# Edge_Connector.net
KiCad netlist of a schematic drawn in Altium Designer
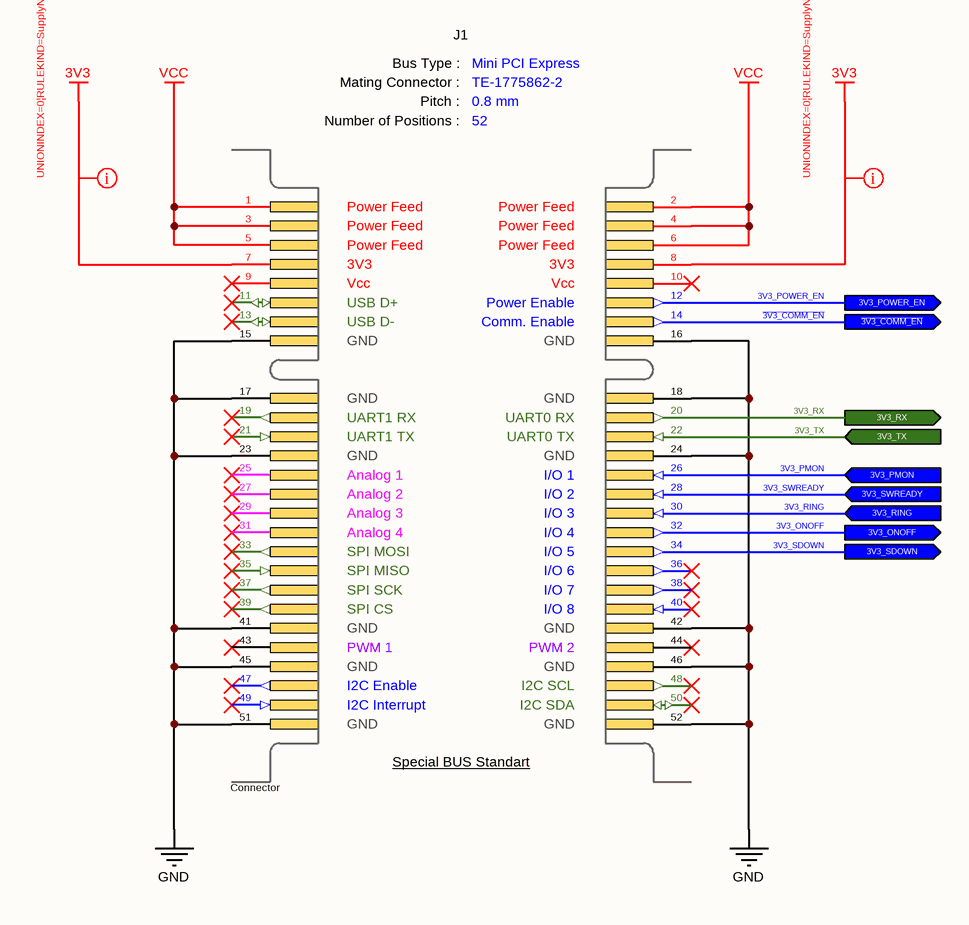
[diagram p0: Edge_Connector.SchDoc]

(export (version "E")
  (design (tool "Eeschema 10.0.6"))
  (components
    (comp (ref "J1")
      (value "Connector - Mini PCI-E [Add-on]")
      (footprint "PCB - Mini PCI Express")
      (description "Mini PCI-Express gold finger connector.")
      (fields
        (field (name "BUS TYPE") "Mini PCI Express")
        (field (name "MATING CONNECTOR") "TE-1775862-2")
        (field (name "PITCH") "0.8 mm")
        (field (name "NUMBER OF POSITIONS") "52")
        (field (name "SYSTEM") "Connector")
      )
      (libsource (lib "P101DA_Library") (part "Connector - Mini PCI-E [Add-on]"))
    )
  )
  (nets
    (net (code "1") (name "/3V3_ONOFF") (class "Default")
      (node (ref "J1") (pin "32") (pinfunction "Pin-32_32") (pintype "output"))
    )
    (net (code "2") (name "/3V3_PMON") (class "Default")
      (node (ref "J1") (pin "26") (pinfunction "Pin-26_26") (pintype "input"))
    )
    (net (code "3") (name "/3V3_POWER_EN") (class "Default")
      (node (ref "J1") (pin "12") (pinfunction "Pin-12_12") (pintype "output"))
    )
    (net (code "4") (name "/3V3_RING") (class "Default")
      (node (ref "J1") (pin "30") (pinfunction "Pin-30_30") (pintype "input"))
    )
    (net (code "5") (name "/3V3_RX") (class "Default")
      (node (ref "J1") (pin "20") (pinfunction "Pin-20_20") (pintype "output"))
    )
    (net (code "6") (name "/3V3_SDOWN") (class "Default")
      (node (ref "J1") (pin "34") (pinfunction "Pin-34_34") (pintype "output"))
    )
    (net (code "7") (name "/3V3_SWREADY") (class "Default")
      (node (ref "J1") (pin "28") (pinfunction "Pin-28_28") (pintype "input"))
    )
    (net (code "8") (name "/3V3_TX") (class "Default")
      (node (ref "J1") (pin "22") (pinfunction "Pin-22_22") (pintype "input"))
    )
    (net (code "9") (name "/~{3V3_COMM_EN}") (class "Default")
      (node (ref "J1") (pin "14") (pinfunction "Pin-14_14") (pintype "output"))
    )
    (net (code "10") (name "3V3") (class "Default")
      (node (ref "J1") (pin "7") (pinfunction "Pin-7_7") (pintype "power_in"))
      (node (ref "J1") (pin "8") (pinfunction "Pin-8_8") (pintype "power_in"))
    )
    (net (code "11") (name "GND") (class "Default")
      (node (ref "J1") (pin "15") (pinfunction "Pin-15_15") (pintype "power_in"))
      (node (ref "J1") (pin "16") (pinfunction "Pin-16_16") (pintype "power_in"))
      (node (ref "J1") (pin "17") (pinfunction "Pin-17_17") (pintype "power_in"))
      (node (ref "J1") (pin "18") (pinfunction "Pin-18_18") (pintype "power_in"))
      (node (ref "J1") (pin "23") (pinfunction "Pin-23_23") (pintype "power_in"))
      (node (ref "J1") (pin "24") (pinfunction "Pin-24_24") (pintype "power_in"))
      (node (ref "J1") (pin "41") (pinfunction "Pin-41_41") (pintype "power_in"))
      (node (ref "J1") (pin "42") (pinfunction "Pin-42_42") (pintype "power_in"))
      (node (ref "J1") (pin "45") (pinfunction "Pin-45_45") (pintype "power_in"))
      (node (ref "J1") (pin "46") (pinfunction "Pin-46_46") (pintype "power_in"))
      (node (ref "J1") (pin "51") (pinfunction "Pin-51_51") (pintype "power_in"))
      (node (ref "J1") (pin "52") (pinfunction "Pin-52_52") (pintype "power_in"))
    )
    (net (code "12") (name "VCC") (class "Default")
      (node (ref "J1") (pin "1") (pinfunction "Pin-1_1") (pintype "power_in"))
      (node (ref "J1") (pin "2") (pinfunction "Pin-2_2") (pintype "power_in"))
      (node (ref "J1") (pin "3") (pinfunction "Pin-3_3") (pintype "power_in"))
      (node (ref "J1") (pin "4") (pinfunction "Pin-4_4") (pintype "power_in"))
      (node (ref "J1") (pin "5") (pinfunction "Pin-5_5") (pintype "power_in"))
      (node (ref "J1") (pin "6") (pinfunction "Pin-6_6") (pintype "power_in"))
    )
    (net (code "13") (name "unconnected-(J1-Pin-9-Pad9)") (class "Default")
      (node (ref "J1") (pin "9") (pinfunction "Pin-9_9") (pintype "power_in+no_connect"))
    )
    (net (code "14") (name "unconnected-(J1-Pin-10-Pad10)") (class "Default")
      (node (ref "J1") (pin "10") (pinfunction "Pin-10_10") (pintype "power_in+no_connect"))
    )
    (net (code "15") (name "unconnected-(J1-Pin-11-Pad11)") (class "Default")
      (node (ref "J1") (pin "11") (pinfunction "Pin-11_11") (pintype "bidirectional+no_connect"))
    )
    (net (code "16") (name "unconnected-(J1-Pin-13-Pad13)") (class "Default")
      (node (ref "J1") (pin "13") (pinfunction "Pin-13_13") (pintype "bidirectional+no_connect"))
    )
    (net (code "17") (name "unconnected-(J1-Pin-19-Pad19)") (class "Default")
      (node (ref "J1") (pin "19") (pinfunction "Pin-19_19") (pintype "output+no_connect"))
    )
    (net (code "18") (name "unconnected-(J1-Pin-21-Pad21)") (class "Default")
      (node (ref "J1") (pin "21") (pinfunction "Pin-21_21") (pintype "input+no_connect"))
    )
    (net (code "19") (name "unconnected-(J1-Pin-25-Pad25)") (class "Default")
      (node (ref "J1") (pin "25") (pinfunction "Pin-25_25") (pintype "passive+no_connect"))
    )
    (net (code "20") (name "unconnected-(J1-Pin-27-Pad27)") (class "Default")
      (node (ref "J1") (pin "27") (pinfunction "Pin-27_27") (pintype "passive+no_connect"))
    )
    (net (code "21") (name "unconnected-(J1-Pin-29-Pad29)") (class "Default")
      (node (ref "J1") (pin "29") (pinfunction "Pin-29_29") (pintype "passive+no_connect"))
    )
    (net (code "22") (name "unconnected-(J1-Pin-31-Pad31)") (class "Default")
      (node (ref "J1") (pin "31") (pinfunction "Pin-31_31") (pintype "passive+no_connect"))
    )
    (net (code "23") (name "unconnected-(J1-Pin-33-Pad33)") (class "Default")
      (node (ref "J1") (pin "33") (pinfunction "Pin-33_33") (pintype "output+no_connect"))
    )
    (net (code "24") (name "unconnected-(J1-Pin-35-Pad35)") (class "Default")
      (node (ref "J1") (pin "35") (pinfunction "Pin-35_35") (pintype "input+no_connect"))
    )
    (net (code "25") (name "unconnected-(J1-Pin-36-Pad36)") (class "Default")
      (node (ref "J1") (pin "36") (pinfunction "Pin-36_36") (pintype "output+no_connect"))
    )
    (net (code "26") (name "unconnected-(J1-Pin-37-Pad37)") (class "Default")
      (node (ref "J1") (pin "37") (pinfunction "Pin-37_37") (pintype "output+no_connect"))
    )
    (net (code "27") (name "unconnected-(J1-Pin-38-Pad38)") (class "Default")
      (node (ref "J1") (pin "38") (pinfunction "Pin-38_38") (pintype "output+no_connect"))
    )
    (net (code "28") (name "unconnected-(J1-Pin-39-Pad39)") (class "Default")
      (node (ref "J1") (pin "39") (pinfunction "Pin-39_39") (pintype "output+no_connect"))
    )
    (net (code "29") (name "unconnected-(J1-Pin-40-Pad40)") (class "Default")
      (node (ref "J1") (pin "40") (pinfunction "Pin-40_40") (pintype "input+no_connect"))
    )
    (net (code "30") (name "unconnected-(J1-Pin-43-Pad43)") (class "Default")
      (node (ref "J1") (pin "43") (pinfunction "Pin-43_43") (pintype "passive+no_connect"))
    )
    (net (code "31") (name "unconnected-(J1-Pin-44-Pad44)") (class "Default")
      (node (ref "J1") (pin "44") (pinfunction "Pin-44_44") (pintype "passive+no_connect"))
    )
    (net (code "32") (name "unconnected-(J1-Pin-47-Pad47)") (class "Default")
      (node (ref "J1") (pin "47") (pinfunction "Pin-47_47") (pintype "output+no_connect"))
    )
    (net (code "33") (name "unconnected-(J1-Pin-48-Pad48)") (class "Default")
      (node (ref "J1") (pin "48") (pinfunction "Pin-48_48") (pintype "output+no_connect"))
    )
    (net (code "34") (name "unconnected-(J1-Pin-49-Pad49)") (class "Default")
      (node (ref "J1") (pin "49") (pinfunction "Pin-49_49") (pintype "input+no_connect"))
    )
    (net (code "35") (name "unconnected-(J1-Pin-50-Pad50)") (class "Default")
      (node (ref "J1") (pin "50") (pinfunction "Pin-50_50") (pintype "bidirectional+no_connect"))
    )
  )
)
